# AS5047P.net
KiCad netlist of a schematic drawn in Altium Designer
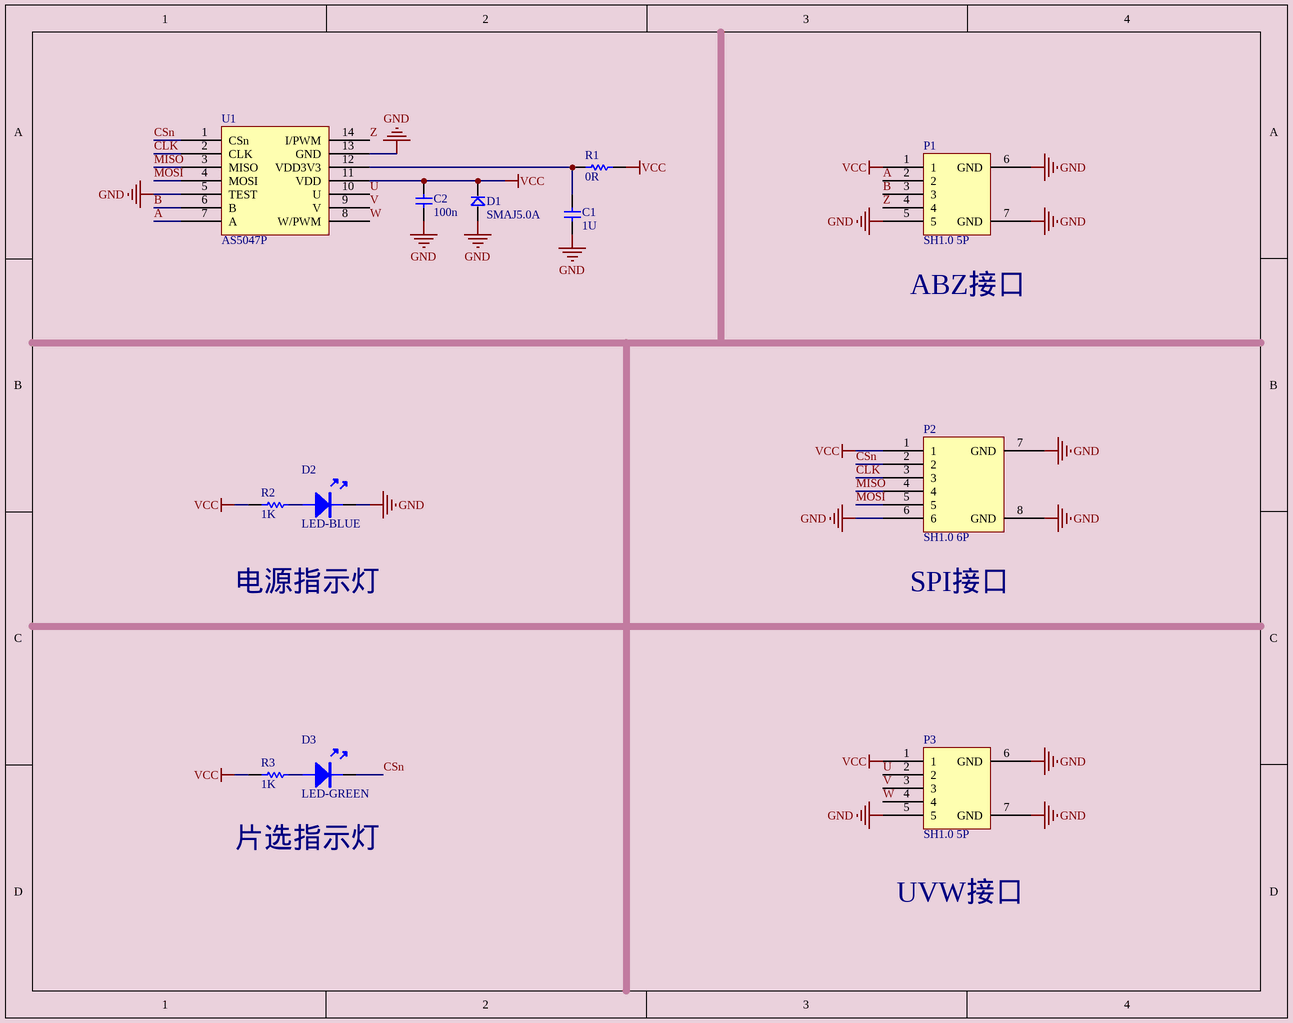
[diagram p0: AS5047P.SchDoc]

(export (version "E")
  (design (tool "Eeschema 10.0.6"))
  (components
    (comp (ref "C1")
      (value "1U")
      (footprint "0603C")
      (description "无极性电容")
      (libsource (lib "电容") (part "CAP"))
    )
    (comp (ref "C2")
      (value "100n")
      (footprint "0603C")
      (description "无极性电容")
      (libsource (lib "电容") (part "CAP"))
    )
    (comp (ref "D1")
      (value "SMAJ5.0A")
      (footprint "SMA/DO-214AC")
      (description "普通二极管")
      (libsource (lib "二极管") (part "DIODE"))
    )
    (comp (ref "D2") (value "LED-BLUE") (footprint "LED-0603B") (libsource (lib "LED") (part "LED")))
    (comp (ref "D3") (value "LED-GREEN") (footprint "LED-0603G") (libsource (lib "LED") (part "LED")))
    (comp (ref "P1")
      (value "SH1.0 5P")
      (footprint "SH1.0 5P")
      (description "SH1.0 5P 卧贴")
      (libsource (lib "AS5047P") (part "SH1.0 5P"))
    )
    (comp (ref "P2")
      (value "SH1.0 6P")
      (footprint "SH1.0 6P")
      (description "SH1.0 6P 卧贴")
      (libsource (lib "AS5047P") (part "SH1.0 6P"))
    )
    (comp (ref "P3")
      (value "SH1.0 5P")
      (footprint "SH1.0 5P")
      (description "SH1.0 5P 卧贴")
      (libsource (lib "AS5047P") (part "SH1.0 5P"))
    )
    (comp (ref "R1") (value "0R") (footprint "0603RH") (libsource (lib "电阻") (part "RES")))
    (comp (ref "R2") (value "1K") (footprint "0603RH") (libsource (lib "电阻") (part "RES")))
    (comp (ref "R3") (value "1K") (footprint "0603RH") (libsource (lib "电阻") (part "RES")))
    (comp (ref "U1")
      (value "AS5047P")
      (footprint "AS5047P")
      (description "AS5047P SSOP14")
      (libsource (lib "AS5047P") (part "AS5047P"))
    )
  )
  (nets
    (net (code "1") (name "/A") (class "Default")
      (node (ref "P1") (pin "2") (pinfunction "2_2") (pintype "passive"))
      (node (ref "U1") (pin "7") (pinfunction "A_7") (pintype "passive"))
    )
    (net (code "2") (name "/B") (class "Default")
      (node (ref "P1") (pin "3") (pinfunction "3_3") (pintype "passive"))
      (node (ref "U1") (pin "6") (pinfunction "B_6") (pintype "passive"))
    )
    (net (code "3") (name "/CLK") (class "Default")
      (node (ref "P2") (pin "3") (pinfunction "3_3") (pintype "passive"))
      (node (ref "U1") (pin "2") (pinfunction "CLK_2") (pintype "passive"))
    )
    (net (code "4") (name "/CSn") (class "Default")
      (node (ref "D3") (pin "K") (pinfunction "K_K") (pintype "passive"))
      (node (ref "P2") (pin "2") (pinfunction "2_2") (pintype "passive"))
      (node (ref "U1") (pin "1") (pinfunction "CSn_1") (pintype "passive"))
    )
    (net (code "5") (name "/MISO") (class "Default")
      (node (ref "P2") (pin "4") (pinfunction "4_4") (pintype "passive"))
      (node (ref "U1") (pin "3") (pinfunction "MISO_3") (pintype "passive"))
    )
    (net (code "6") (name "/MOSI") (class "Default")
      (node (ref "P2") (pin "5") (pinfunction "5_5") (pintype "passive"))
      (node (ref "U1") (pin "4") (pinfunction "MOSI_4") (pintype "passive"))
    )
    (net (code "7") (name "/U") (class "Default")
      (node (ref "P3") (pin "2") (pinfunction "2_2") (pintype "passive"))
      (node (ref "U1") (pin "10") (pinfunction "U_10") (pintype "passive"))
    )
    (net (code "8") (name "/V") (class "Default")
      (node (ref "P3") (pin "3") (pinfunction "3_3") (pintype "passive"))
      (node (ref "U1") (pin "9") (pinfunction "V_9") (pintype "passive"))
    )
    (net (code "9") (name "/W") (class "Default")
      (node (ref "P3") (pin "4") (pinfunction "4_4") (pintype "passive"))
      (node (ref "U1") (pin "8") (pinfunction "W/PWM_8") (pintype "passive"))
    )
    (net (code "10") (name "/Z") (class "Default")
      (node (ref "P1") (pin "4") (pinfunction "4_4") (pintype "passive"))
      (node (ref "U1") (pin "14") (pinfunction "I/PWM_14") (pintype "passive"))
    )
    (net (code "11") (name "GND") (class "Default")
      (node (ref "C1") (pin "1") (pinfunction "1_1") (pintype "passive"))
      (node (ref "C2") (pin "1") (pinfunction "1_1") (pintype "passive"))
      (node (ref "D1") (pin "A") (pinfunction "A_A") (pintype "passive"))
      (node (ref "D2") (pin "K") (pinfunction "K_K") (pintype "passive"))
      (node (ref "P1") (pin "5") (pinfunction "5_5") (pintype "passive"))
      (node (ref "P1") (pin "6") (pinfunction "GND_6") (pintype "passive"))
      (node (ref "P1") (pin "7") (pinfunction "GND_7") (pintype "passive"))
      (node (ref "P2") (pin "6") (pinfunction "6_6") (pintype "passive"))
      (node (ref "P2") (pin "7") (pinfunction "GND_7") (pintype "passive"))
      (node (ref "P2") (pin "8") (pinfunction "GND_8") (pintype "passive"))
      (node (ref "P3") (pin "5") (pinfunction "5_5") (pintype "passive"))
      (node (ref "P3") (pin "6") (pinfunction "GND_6") (pintype "passive"))
      (node (ref "P3") (pin "7") (pinfunction "GND_7") (pintype "passive"))
      (node (ref "U1") (pin "13") (pinfunction "GND_13") (pintype "passive"))
      (node (ref "U1") (pin "5") (pinfunction "TEST_5") (pintype "passive"))
    )
    (net (code "12") (name "Net-(D2-PadA)") (class "Default")
      (node (ref "D2") (pin "A") (pinfunction "A_A") (pintype "passive"))
      (node (ref "R2") (pin "2") (pinfunction "2_2") (pintype "passive"))
    )
    (net (code "13") (name "Net-(D3-PadA)") (class "Default")
      (node (ref "D3") (pin "A") (pinfunction "A_A") (pintype "passive"))
      (node (ref "R3") (pin "2") (pinfunction "2_2") (pintype "passive"))
    )
    (net (code "14") (name "Net-(U1-VDD3V3)") (class "Default")
      (node (ref "C1") (pin "2") (pinfunction "2_2") (pintype "passive"))
      (node (ref "R1") (pin "1") (pinfunction "1_1") (pintype "passive"))
      (node (ref "U1") (pin "12") (pinfunction "VDD3V3_12") (pintype "passive"))
    )
    (net (code "15") (name "VCC") (class "Default")
      (node (ref "C2") (pin "2") (pinfunction "2_2") (pintype "passive"))
      (node (ref "D1") (pin "K") (pinfunction "K_K") (pintype "passive"))
      (node (ref "P1") (pin "1") (pinfunction "1_1") (pintype "passive"))
      (node (ref "P2") (pin "1") (pinfunction "1_1") (pintype "passive"))
      (node (ref "P3") (pin "1") (pinfunction "1_1") (pintype "passive"))
      (node (ref "R1") (pin "2") (pinfunction "2_2") (pintype "passive"))
      (node (ref "R2") (pin "1") (pinfunction "1_1") (pintype "passive"))
      (node (ref "R3") (pin "1") (pinfunction "1_1") (pintype "passive"))
      (node (ref "U1") (pin "11") (pinfunction "VDD_11") (pintype "passive"))
    )
  )
)
